# STlinkv21.net
KiCad netlist of a schematic drawn in Altium Designer
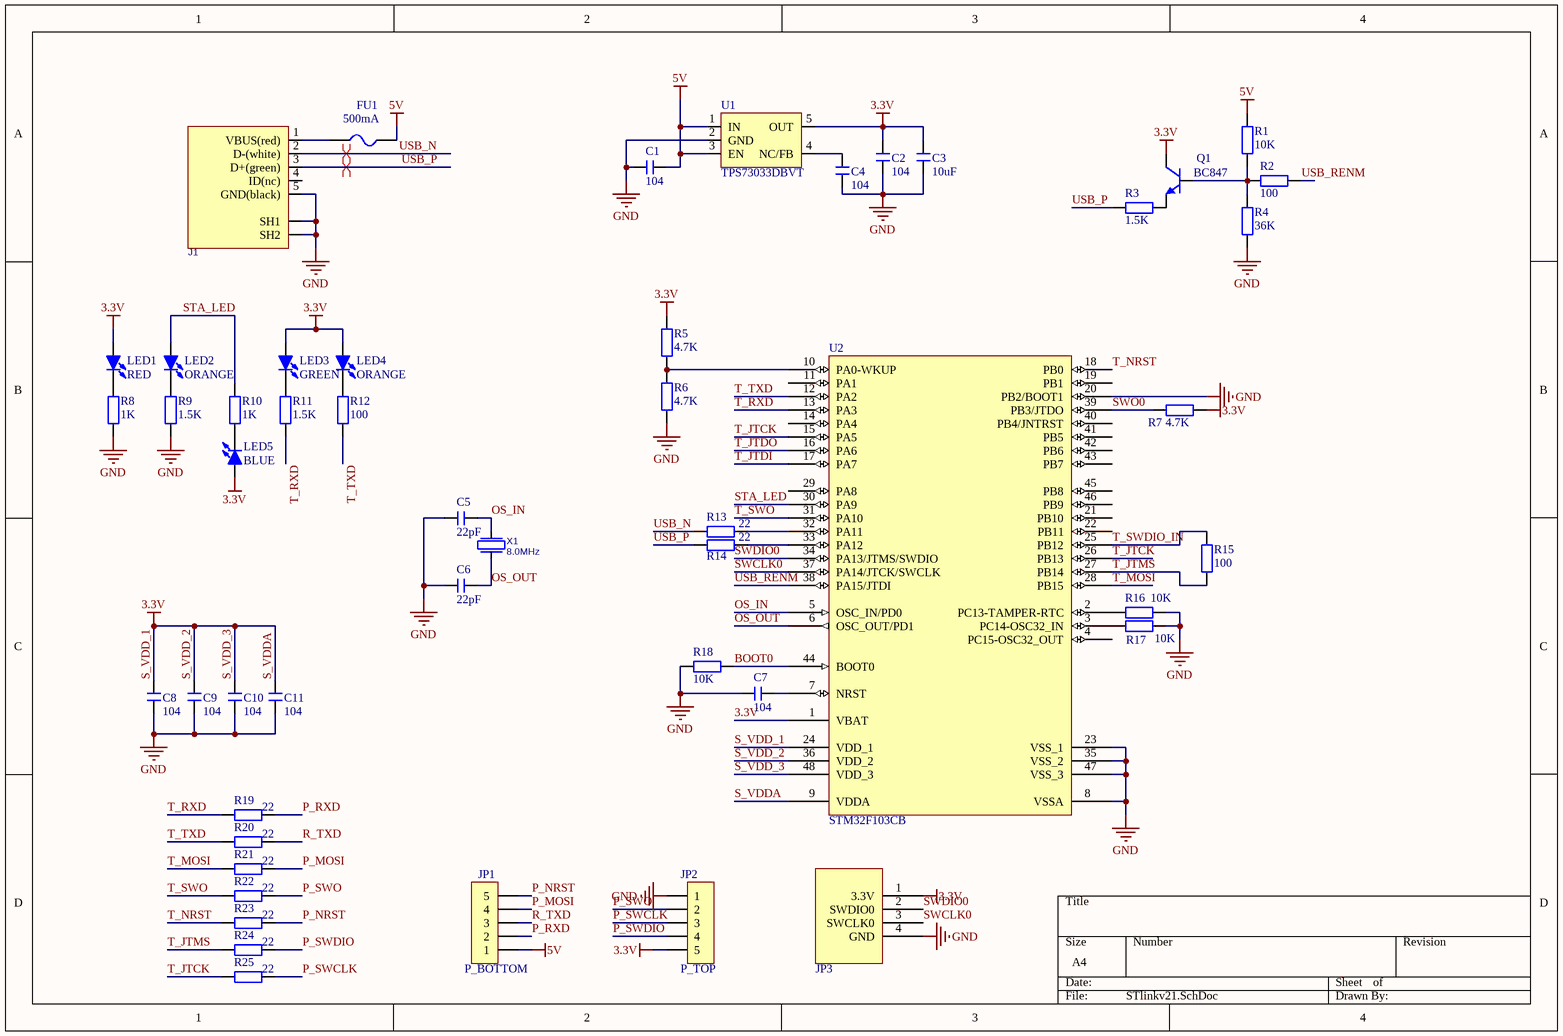
[diagram p0: STlinkv21.SchDoc]

(export (version "E")
  (design (tool "Eeschema 10.0.6"))
  (components
    (comp (ref "*") (value "JP3") (footprint "JP4") (libsource (lib "STlinkv21") (part "JP?")))
    (comp (ref "C1")
      (value "104")
      (footprint "C 0603_L")
      (description "无极性贴片电容")
      (fields (field (name "版权归属") "源创客"))
      (libsource (lib "3.1   - 电阻-电容-电感") (part "C"))
    )
    (comp (ref "C2")
      (value "104")
      (footprint "C 0603_L")
      (description "无极性贴片电容")
      (fields (field (name "版权归属") "源创客"))
      (libsource (lib "3.1   - 电阻-电容-电感") (part "C"))
    )
    (comp (ref "C3")
      (value "10uF")
      (footprint "C 0603_L")
      (description "无极性贴片电容")
      (fields (field (name "版权归属") "源创客"))
      (libsource (lib "3.1   - 电阻-电容-电感") (part "C"))
    )
    (comp (ref "C4")
      (value "104")
      (footprint "C 0603_L")
      (description "无极性贴片电容")
      (fields (field (name "版权归属") "源创客"))
      (libsource (lib "3.1   - 电阻-电容-电感") (part "C"))
    )
    (comp (ref "C5")
      (value "22pF")
      (footprint "C 0603_L")
      (description "无极性贴片电容")
      (fields (field (name "版权归属") "源创客"))
      (libsource (lib "3.1   - 电阻-电容-电感") (part "C"))
    )
    (comp (ref "C6")
      (value "22pF")
      (footprint "C 0603_L")
      (description "无极性贴片电容")
      (fields (field (name "版权归属") "源创客"))
      (libsource (lib "3.1   - 电阻-电容-电感") (part "C"))
    )
    (comp (ref "C7")
      (value "104")
      (footprint "C 0603_L")
      (description "无极性贴片电容")
      (fields (field (name "版权归属") "源创客"))
      (libsource (lib "3.1   - 电阻-电容-电感") (part "C"))
    )
    (comp (ref "C8")
      (value "104")
      (footprint "C 0603_L")
      (description "无极性贴片电容")
      (fields (field (name "版权归属") "源创客"))
      (libsource (lib "3.1   - 电阻-电容-电感") (part "C"))
    )
    (comp (ref "C9")
      (value "104")
      (footprint "C 0603_L")
      (description "无极性贴片电容")
      (fields (field (name "版权归属") "源创客"))
      (libsource (lib "3.1   - 电阻-电容-电感") (part "C"))
    )
    (comp (ref "C10")
      (value "104")
      (footprint "C 0603_L")
      (description "无极性贴片电容")
      (fields (field (name "版权归属") "源创客"))
      (libsource (lib "3.1   - 电阻-电容-电感") (part "C"))
    )
    (comp (ref "C11")
      (value "104")
      (footprint "C 0603_L")
      (description "无极性贴片电容")
      (fields (field (name "版权归属") "源创客"))
      (libsource (lib "3.1   - 电阻-电容-电感") (part "C"))
    )
    (comp (ref "FU1")
      (value "500mA")
      (footprint "FU 0805")
      (description "贴片保险丝")
      (fields (field (name "版权归属") "源创客"))
      (libsource (lib "10.1 - 保险丝-晶振") (part "FU"))
    )
    (comp (ref "J1")
      (value "microUSB 5BFR")
      (footprint "usbmicro B")
      (fields (field (name "LIBRARYNAME") "Nikitin (Exeland)"))
      (libsource (lib "Nikitin") (part "microUSB 5BFR"))
    )
    (comp (ref "JP1")
      (value "P_BOTTOM")
      (footprint "JP5Bottom")
      (description "5P接插件")
      (fields (field (name "版权归属") "源创客"))
      (libsource (lib "") (part "Header 5_1"))
    )
    (comp (ref "JP2")
      (value "P_TOP")
      (footprint "JP5TOP")
      (description "5P接插件")
      (fields (field (name "版权归属") "源创客"))
      (libsource (lib "4.5   - 接插件-脚距2.54") (part "Header 5"))
    )
    (comp (ref "LED1")
      (value "RED")
      (footprint "LED 0603B")
      (description "贴片LED")
      (fields (field (name "版权归属") "源创客"))
      (libsource (lib "9.1   - LED") (part "LED-SMD"))
    )
    (comp (ref "LED2")
      (value "ORANGE")
      (footprint "LED 0603B")
      (description "贴片LED")
      (fields (field (name "版权归属") "源创客"))
      (libsource (lib "9.1   - LED") (part "LED-SMD"))
    )
    (comp (ref "LED3")
      (value "GREEN")
      (footprint "LED 0603B")
      (description "贴片LED")
      (fields (field (name "版权归属") "源创客"))
      (libsource (lib "9.1   - LED") (part "LED-SMD"))
    )
    (comp (ref "LED4")
      (value "ORANGE")
      (footprint "LED 0603B")
      (description "贴片LED")
      (fields (field (name "版权归属") "源创客"))
      (libsource (lib "9.1   - LED") (part "LED-SMD"))
    )
    (comp (ref "LED5")
      (value "BLUE")
      (footprint "LED 0603B")
      (description "贴片LED")
      (fields (field (name "版权归属") "LED 0603 BLUE"))
      (libsource (lib "9.1   - LED") (part "LED-SMD"))
    )
    (comp (ref "Q1")
      (value "BC847")
      (footprint "SOT23-3N")
      (description "高频放大-NPN型")
      (fields (field (name "版权归属") "源创客"))
      (libsource (lib "6.2   - 三极管") (part "8050-SMD"))
    )
    (comp (ref "R1")
      (value "10K")
      (footprint "R 0603_L")
      (description "贴片电阻")
      (fields (field (name "版权归属") "源创客"))
      (libsource (lib "3.1   - 电阻-电容-电感") (part "R"))
    )
    (comp (ref "R2")
      (value "100")
      (footprint "R 0603_L")
      (description "贴片电阻")
      (fields (field (name "版权归属") "源创客"))
      (libsource (lib "3.1   - 电阻-电容-电感") (part "R"))
    )
    (comp (ref "R3")
      (value "1.5K")
      (footprint "R 0603_L")
      (description "贴片电阻")
      (fields (field (name "版权归属") "源创客"))
      (libsource (lib "3.1   - 电阻-电容-电感") (part "R"))
    )
    (comp (ref "R4")
      (value "36K")
      (footprint "R 0603_L")
      (description "贴片电阻")
      (fields (field (name "版权归属") "源创客"))
      (libsource (lib "3.1   - 电阻-电容-电感") (part "R"))
    )
    (comp (ref "R5")
      (value "4.7K")
      (footprint "R 0603_L")
      (description "贴片电阻")
      (fields (field (name "版权归属") "源创客"))
      (libsource (lib "3.1   - 电阻-电容-电感") (part "R"))
    )
    (comp (ref "R6")
      (value "4.7K")
      (footprint "R 0603_L")
      (description "贴片电阻")
      (fields (field (name "版权归属") "源创客"))
      (libsource (lib "3.1   - 电阻-电容-电感") (part "R"))
    )
    (comp (ref "R7")
      (value "4.7K")
      (footprint "R 0603_L")
      (description "贴片电阻")
      (fields (field (name "版权归属") "源创客"))
      (libsource (lib "3.1   - 电阻-电容-电感") (part "R"))
    )
    (comp (ref "R8")
      (value "1K")
      (footprint "R 0603_L")
      (description "贴片电阻")
      (fields (field (name "版权归属") "源创客"))
      (libsource (lib "3.1   - 电阻-电容-电感") (part "R"))
    )
    (comp (ref "R9")
      (value "1.5K")
      (footprint "R 0603_L")
      (description "贴片电阻")
      (fields (field (name "版权归属") "源创客"))
      (libsource (lib "3.1   - 电阻-电容-电感") (part "R"))
    )
    (comp (ref "R10")
      (value "1K")
      (footprint "R 0603_L")
      (description "贴片电阻")
      (fields (field (name "版权归属") "源创客"))
      (libsource (lib "3.1   - 电阻-电容-电感") (part "R"))
    )
    (comp (ref "R11")
      (value "1.5K")
      (footprint "R 0603_L")
      (description "贴片电阻")
      (fields (field (name "版权归属") "源创客"))
      (libsource (lib "3.1   - 电阻-电容-电感") (part "R"))
    )
    (comp (ref "R12")
      (value "100")
      (footprint "R 0603_L")
      (description "贴片电阻")
      (fields (field (name "版权归属") "源创客"))
      (libsource (lib "3.1   - 电阻-电容-电感") (part "R"))
    )
    (comp (ref "R13")
      (value "22")
      (footprint "R 0603_L")
      (description "贴片电阻")
      (fields (field (name "版权归属") "源创客"))
      (libsource (lib "3.1   - 电阻-电容-电感") (part "R"))
    )
    (comp (ref "R14")
      (value "22")
      (footprint "R 0603_L")
      (description "贴片电阻")
      (fields (field (name "版权归属") "源创客"))
      (libsource (lib "3.1   - 电阻-电容-电感") (part "R"))
    )
    (comp (ref "R15")
      (value "100")
      (footprint "R 0603_L")
      (description "贴片电阻")
      (fields (field (name "版权归属") "源创客"))
      (libsource (lib "3.1   - 电阻-电容-电感") (part "R"))
    )
    (comp (ref "R16")
      (value "10K")
      (footprint "R 0603_L")
      (description "贴片电阻")
      (fields (field (name "版权归属") "源创客"))
      (libsource (lib "3.1   - 电阻-电容-电感") (part "R"))
    )
    (comp (ref "R17")
      (value "10K")
      (footprint "R 0603_L")
      (description "贴片电阻")
      (fields (field (name "版权归属") "源创客"))
      (libsource (lib "3.1   - 电阻-电容-电感") (part "R"))
    )
    (comp (ref "R18")
      (value "10K")
      (footprint "R 0603_L")
      (description "贴片电阻")
      (fields (field (name "版权归属") "源创客"))
      (libsource (lib "3.1   - 电阻-电容-电感") (part "R"))
    )
    (comp (ref "R19")
      (value "22")
      (footprint "R 0603_L")
      (description "贴片电阻")
      (fields (field (name "版权归属") "源创客"))
      (libsource (lib "3.1   - 电阻-电容-电感") (part "R"))
    )
    (comp (ref "R20")
      (value "22")
      (footprint "R 0603_L")
      (description "贴片电阻")
      (fields (field (name "版权归属") "源创客"))
      (libsource (lib "3.1   - 电阻-电容-电感") (part "R"))
    )
    (comp (ref "R21")
      (value "22")
      (footprint "R 0603_L")
      (description "贴片电阻")
      (fields (field (name "版权归属") "源创客"))
      (libsource (lib "3.1   - 电阻-电容-电感") (part "R"))
    )
    (comp (ref "R22")
      (value "22")
      (footprint "R 0603_L")
      (description "贴片电阻")
      (fields (field (name "版权归属") "源创客"))
      (libsource (lib "3.1   - 电阻-电容-电感") (part "R"))
    )
    (comp (ref "R23")
      (value "22")
      (footprint "R 0603_L")
      (description "贴片电阻")
      (fields (field (name "版权归属") "源创客"))
      (libsource (lib "3.1   - 电阻-电容-电感") (part "R"))
    )
    (comp (ref "R24")
      (value "22")
      (footprint "R 0603_L")
      (description "贴片电阻")
      (fields (field (name "版权归属") "源创客"))
      (libsource (lib "3.1   - 电阻-电容-电感") (part "R"))
    )
    (comp (ref "R25")
      (value "22")
      (footprint "R 0603_L")
      (description "贴片电阻")
      (fields (field (name "版权归属") "源创客"))
      (libsource (lib "3.1   - 电阻-电容-电感") (part "R"))
    )
    (comp (ref "U1")
      (value "TPS73033DBVT")
      (footprint "SOT-23-5")
      (fields (field (name "LIBRARYNAME") "Nikitin (Exeland)"))
      (libsource (lib "Nikitin") (part "TPS73033DBVT"))
    )
    (comp (ref "U2")
      (value "STM32F103CB")
      (footprint "LQFP48 7X7_L")
      (description "Flaah:64/RAM:20/IO:36")
      (fields (field (name "版权归属") "源创客"))
      (libsource (lib "2.1   - STM32系列单片机") (part "STM32F103C8"))
    )
    (comp (ref "X1")
      (value "8.0MHz")
      (footprint "HC49SMD")
      (description "8 MHz ±20ppm Crystal 18pF 80 Ohms HC-49/US")
      (fields (field (name "Comment") "HC49SM") (field (name "LIBRARYNAME") "Nikitin (Exeland)"))
      (libsource (lib "Nikitin") (part "HC49SM"))
    )
  )
  (nets
    (net (code "1") (name "/BOOT0") (class "Default")
      (node (ref "R18") (pin "1") (pinfunction "1_1") (pintype "passive"))
      (node (ref "U2") (pin "44") (pinfunction "BOOT0_44") (pintype "input"))
    )
    (net (code "2") (name "/OS_IN") (class "Default")
      (node (ref "C5") (pin "2") (pinfunction "2_2") (pintype "passive"))
      (node (ref "U2") (pin "5") (pinfunction "OSC_IN/PD0_5") (pintype "input"))
      (node (ref "X1") (pin "2") (pintype "passive"))
    )
    (net (code "3") (name "/OS_OUT") (class "Default")
      (node (ref "C6") (pin "2") (pinfunction "2_2") (pintype "passive"))
      (node (ref "U2") (pin "6") (pinfunction "OSC_OUT/PD1_6") (pintype "output"))
      (node (ref "X1") (pin "1") (pintype "passive"))
    )
    (net (code "4") (name "/P_MOSI") (class "Default")
      (node (ref "JP1") (pin "4") (pinfunction "4_4") (pintype "passive"))
      (node (ref "R21") (pin "1") (pinfunction "1_1") (pintype "passive"))
    )
    (net (code "5") (name "/P_NRST") (class "Default")
      (node (ref "JP1") (pin "5") (pinfunction "5_5") (pintype "passive"))
      (node (ref "R23") (pin "1") (pinfunction "1_1") (pintype "passive"))
    )
    (net (code "6") (name "/P_RXD") (class "Default")
      (node (ref "JP1") (pin "2") (pinfunction "2_2") (pintype "passive"))
      (node (ref "R19") (pin "1") (pinfunction "1_1") (pintype "passive"))
    )
    (net (code "7") (name "/P_SWCLK") (class "Default")
      (node (ref "JP2") (pin "3") (pinfunction "3_3") (pintype "passive"))
      (node (ref "R25") (pin "1") (pinfunction "1_1") (pintype "passive"))
    )
    (net (code "8") (name "/P_SWDIO") (class "Default")
      (node (ref "JP2") (pin "4") (pinfunction "4_4") (pintype "passive"))
      (node (ref "R24") (pin "1") (pinfunction "1_1") (pintype "passive"))
    )
    (net (code "9") (name "/P_SWO") (class "Default")
      (node (ref "JP2") (pin "2") (pinfunction "2_2") (pintype "passive"))
      (node (ref "R22") (pin "1") (pinfunction "1_1") (pintype "passive"))
    )
    (net (code "10") (name "/R_TXD") (class "Default")
      (node (ref "JP1") (pin "3") (pinfunction "3_3") (pintype "passive"))
      (node (ref "R20") (pin "1") (pinfunction "1_1") (pintype "passive"))
    )
    (net (code "11") (name "/STA_LED") (class "Default")
      (node (ref "LED2") (pin "1") (pinfunction "A_1") (pintype "passive"))
      (node (ref "R10") (pin "2") (pinfunction "2_2") (pintype "passive"))
      (node (ref "U2") (pin "30") (pinfunction "PA9_30") (pintype "bidirectional"))
    )
    (net (code "12") (name "/SWCLK0") (class "Default")
      (node (ref "*") (pin "3") (pinfunction "SWCLK0_3") (pintype "passive"))
      (node (ref "U2") (pin "37") (pinfunction "PA14/JTCK/SWCLK_37") (pintype "bidirectional"))
    )
    (net (code "13") (name "/SWDIO0") (class "Default")
      (node (ref "*") (pin "2") (pinfunction "SWDIO0_2") (pintype "passive"))
      (node (ref "U2") (pin "34") (pinfunction "PA13/JTMS/SWDIO_34") (pintype "bidirectional"))
    )
    (net (code "14") (name "/SWO0") (class "Default")
      (node (ref "R7") (pin "1") (pinfunction "1_1") (pintype "passive"))
      (node (ref "U2") (pin "39") (pinfunction "PB3/JTDO_39") (pintype "bidirectional"))
    )
    (net (code "15") (name "/T_JTCK") (class "Default")
      (node (ref "R25") (pin "2") (pinfunction "2_2") (pintype "passive"))
      (node (ref "U2") (pin "15") (pinfunction "PA5_15") (pintype "bidirectional"))
      (node (ref "U2") (pin "26") (pinfunction "PB13_26") (pintype "bidirectional"))
    )
    (net (code "16") (name "/T_JTDI") (class "Default")
      (node (ref "U2") (pin "17") (pinfunction "PA7_17") (pintype "bidirectional"))
    )
    (net (code "17") (name "/T_JTDO") (class "Default")
      (node (ref "U2") (pin "16") (pinfunction "PA6_16") (pintype "bidirectional"))
    )
    (net (code "18") (name "/T_JTMS") (class "Default")
      (node (ref "R15") (pin "2") (pinfunction "2_2") (pintype "passive"))
      (node (ref "R24") (pin "2") (pinfunction "2_2") (pintype "passive"))
      (node (ref "U2") (pin "27") (pinfunction "PB14_27") (pintype "bidirectional"))
    )
    (net (code "19") (name "/T_MOSI") (class "Default")
      (node (ref "R21") (pin "2") (pinfunction "2_2") (pintype "passive"))
      (node (ref "U2") (pin "28") (pinfunction "PB15_28") (pintype "bidirectional"))
    )
    (net (code "20") (name "/T_NRST") (class "Default")
      (node (ref "R23") (pin "2") (pinfunction "2_2") (pintype "passive"))
      (node (ref "U2") (pin "18") (pinfunction "PB0_18") (pintype "bidirectional"))
    )
    (net (code "21") (name "/T_RXD") (class "Default")
      (node (ref "R11") (pin "1") (pinfunction "1_1") (pintype "passive"))
      (node (ref "R19") (pin "2") (pinfunction "2_2") (pintype "passive"))
      (node (ref "U2") (pin "13") (pinfunction "PA3_13") (pintype "bidirectional"))
    )
    (net (code "22") (name "/T_SWDIO_IN") (class "Default")
      (node (ref "R15") (pin "1") (pinfunction "1_1") (pintype "passive"))
      (node (ref "U2") (pin "25") (pinfunction "PB12_25") (pintype "bidirectional"))
    )
    (net (code "23") (name "/T_SWO") (class "Default")
      (node (ref "R22") (pin "2") (pinfunction "2_2") (pintype "passive"))
      (node (ref "U2") (pin "31") (pinfunction "PA10_31") (pintype "bidirectional"))
    )
    (net (code "24") (name "/T_TXD") (class "Default")
      (node (ref "R12") (pin "1") (pinfunction "1_1") (pintype "passive"))
      (node (ref "R20") (pin "2") (pinfunction "2_2") (pintype "passive"))
      (node (ref "U2") (pin "12") (pinfunction "PA2_12") (pintype "bidirectional"))
    )
    (net (code "25") (name "/USB_N") (class "Default")
      (node (ref "J1") (pin "2") (pinfunction "D-(white)_2") (pintype "passive"))
      (node (ref "R13") (pin "2") (pinfunction "2_2") (pintype "passive"))
    )
    (net (code "26") (name "/USB_P") (class "Default")
      (node (ref "J1") (pin "3") (pinfunction "D+(green)_3") (pintype "passive"))
      (node (ref "R14") (pin "2") (pinfunction "2_2") (pintype "passive"))
      (node (ref "R3") (pin "1") (pinfunction "1_1") (pintype "passive"))
    )
    (net (code "27") (name "/USB_RENM") (class "Default")
      (node (ref "R2") (pin "2") (pinfunction "2_2") (pintype "passive"))
      (node (ref "U2") (pin "38") (pinfunction "PA15/JTDI_38") (pintype "bidirectional"))
    )
    (net (code "28") (name "3.3V") (class "Default")
      (node (ref "*") (pin "1") (pinfunction "3.3V_1") (pintype "passive"))
      (node (ref "C10") (pin "2") (pinfunction "2_2") (pintype "passive"))
      (node (ref "C11") (pin "2") (pinfunction "2_2") (pintype "passive"))
      (node (ref "C2") (pin "2") (pinfunction "2_2") (pintype "passive"))
      (node (ref "C3") (pin "2") (pinfunction "2_2") (pintype "passive"))
      (node (ref "C8") (pin "2") (pinfunction "2_2") (pintype "passive"))
      (node (ref "C9") (pin "2") (pinfunction "2_2") (pintype "passive"))
      (node (ref "JP2") (pin "5") (pinfunction "5_5") (pintype "passive"))
      (node (ref "LED1") (pin "1") (pinfunction "A_1") (pintype "passive"))
      (node (ref "LED3") (pin "1") (pinfunction "A_1") (pintype "passive"))
      (node (ref "LED4") (pin "1") (pinfunction "A_1") (pintype "passive"))
      (node (ref "LED5") (pin "1") (pinfunction "A_1") (pintype "passive"))
      (node (ref "Q1") (pin "3") (pinfunction "C_3") (pintype "passive"))
      (node (ref "R5") (pin "2") (pinfunction "2_2") (pintype "passive"))
      (node (ref "R7") (pin "2") (pinfunction "2_2") (pintype "passive"))
      (node (ref "U1") (pin "5") (pinfunction "OUT_5") (pintype "passive"))
      (node (ref "U2") (pin "1") (pinfunction "VBAT_1") (pintype "power_in"))
      (node (ref "U2") (pin "24") (pinfunction "VDD_1_24") (pintype "power_in"))
      (node (ref "U2") (pin "36") (pinfunction "VDD_2_36") (pintype "power_in"))
      (node (ref "U2") (pin "48") (pinfunction "VDD_3_48") (pintype "power_in"))
      (node (ref "U2") (pin "9") (pinfunction "VDDA_9") (pintype "power_in"))
    )
    (net (code "29") (name "5V") (class "Default")
      (node (ref "C1") (pin "2") (pinfunction "2_2") (pintype "passive"))
      (node (ref "FU1") (pin "2") (pinfunction "2_2") (pintype "passive"))
      (node (ref "JP1") (pin "1") (pinfunction "1_1") (pintype "passive"))
      (node (ref "R1") (pin "2") (pinfunction "2_2") (pintype "passive"))
      (node (ref "U1") (pin "1") (pinfunction "IN_1") (pintype "passive"))
      (node (ref "U1") (pin "3") (pinfunction "EN_3") (pintype "passive"))
    )
    (net (code "30") (name "GND") (class "Default")
      (node (ref "*") (pin "4") (pinfunction "GND_4") (pintype "passive"))
      (node (ref "C1") (pin "1") (pinfunction "1_1") (pintype "passive"))
      (node (ref "C10") (pin "1") (pinfunction "1_1") (pintype "passive"))
      (node (ref "C11") (pin "1") (pinfunction "1_1") (pintype "passive"))
      (node (ref "C2") (pin "1") (pinfunction "1_1") (pintype "passive"))
      (node (ref "C3") (pin "1") (pinfunction "1_1") (pintype "passive"))
      (node (ref "C4") (pin "1") (pinfunction "1_1") (pintype "passive"))
      (node (ref "C5") (pin "1") (pinfunction "1_1") (pintype "passive"))
      (node (ref "C6") (pin "1") (pinfunction "1_1") (pintype "passive"))
      (node (ref "C7") (pin "1") (pinfunction "1_1") (pintype "passive"))
      (node (ref "C8") (pin "1") (pinfunction "1_1") (pintype "passive"))
      (node (ref "C9") (pin "1") (pinfunction "1_1") (pintype "passive"))
      (node (ref "J1") (pin "11") (pinfunction "SH2_11") (pintype "passive"))
      (node (ref "J1") (pin "5") (pinfunction "GND(black)_5") (pintype "passive"))
      (node (ref "J1") (pin "8") (pinfunction "SH1_8") (pintype "passive"))
      (node (ref "JP2") (pin "1") (pinfunction "1_1") (pintype "passive"))
      (node (ref "R16") (pin "1") (pinfunction "1_1") (pintype "passive"))
      (node (ref "R17") (pin "1") (pinfunction "1_1") (pintype "passive"))
      (node (ref "R18") (pin "2") (pinfunction "2_2") (pintype "passive"))
      (node (ref "R4") (pin "1") (pinfunction "1_1") (pintype "passive"))
      (node (ref "R6") (pin "1") (pinfunction "1_1") (pintype "passive"))
      (node (ref "R8") (pin "1") (pinfunction "1_1") (pintype "passive"))
      (node (ref "R9") (pin "1") (pinfunction "1_1") (pintype "passive"))
      (node (ref "U1") (pin "2") (pinfunction "GND_2") (pintype "passive"))
      (node (ref "U2") (pin "20") (pinfunction "PB2/BOOT1_20") (pintype "bidirectional"))
      (node (ref "U2") (pin "23") (pinfunction "VSS_1_23") (pintype "power_in"))
      (node (ref "U2") (pin "35") (pinfunction "VSS_2_35") (pintype "power_in"))
      (node (ref "U2") (pin "47") (pinfunction "VSS_3_47") (pintype "power_in"))
      (node (ref "U2") (pin "8") (pinfunction "VSSA_8") (pintype "power_in"))
    )
    (net (code "31") (name "Net-(J1-VBUS(red))") (class "Default")
      (node (ref "FU1") (pin "1") (pinfunction "1_1") (pintype "passive"))
      (node (ref "J1") (pin "1") (pinfunction "VBUS(red)_1") (pintype "passive"))
    )
    (net (code "32") (name "Net-(LED1-K)") (class "Default")
      (node (ref "LED1") (pin "2") (pinfunction "K_2") (pintype "passive"))
      (node (ref "R8") (pin "2") (pinfunction "2_2") (pintype "passive"))
    )
    (net (code "33") (name "Net-(LED2-K)") (class "Default")
      (node (ref "LED2") (pin "2") (pinfunction "K_2") (pintype "passive"))
      (node (ref "R9") (pin "2") (pinfunction "2_2") (pintype "passive"))
    )
    (net (code "34") (name "Net-(LED3-K)") (class "Default")
      (node (ref "LED3") (pin "2") (pinfunction "K_2") (pintype "passive"))
      (node (ref "R11") (pin "2") (pinfunction "2_2") (pintype "passive"))
    )
    (net (code "35") (name "Net-(LED4-K)") (class "Default")
      (node (ref "LED4") (pin "2") (pinfunction "K_2") (pintype "passive"))
      (node (ref "R12") (pin "2") (pinfunction "2_2") (pintype "passive"))
    )
    (net (code "36") (name "Net-(LED5-K)") (class "Default")
      (node (ref "LED5") (pin "2") (pinfunction "K_2") (pintype "passive"))
      (node (ref "R10") (pin "1") (pinfunction "1_1") (pintype "passive"))
    )
    (net (code "37") (name "Net-(Q1-B)") (class "Default")
      (node (ref "Q1") (pin "1") (pinfunction "B_1") (pintype "passive"))
      (node (ref "R1") (pin "1") (pinfunction "1_1") (pintype "passive"))
      (node (ref "R2") (pin "1") (pinfunction "1_1") (pintype "passive"))
      (node (ref "R4") (pin "2") (pinfunction "2_2") (pintype "passive"))
    )
    (net (code "38") (name "Net-(Q1-E)") (class "Default")
      (node (ref "Q1") (pin "2") (pinfunction "E_2") (pintype "passive"))
      (node (ref "R3") (pin "2") (pinfunction "2_2") (pintype "passive"))
    )
    (net (code "39") (name "Net-(U1-NC{slash}FB)") (class "Default")
      (node (ref "C4") (pin "2") (pinfunction "2_2") (pintype "passive"))
      (node (ref "U1") (pin "4") (pinfunction "NC/FB_4") (pintype "passive"))
    )
    (net (code "40") (name "Net-(U2-NRST)") (class "Default")
      (node (ref "C7") (pin "2") (pinfunction "2_2") (pintype "passive"))
      (node (ref "U2") (pin "7") (pinfunction "NRST_7") (pintype "bidirectional"))
    )
    (net (code "41") (name "Net-(U2-PA0-WKUP)") (class "Default")
      (node (ref "R5") (pin "1") (pinfunction "1_1") (pintype "passive"))
      (node (ref "R6") (pin "2") (pinfunction "2_2") (pintype "passive"))
      (node (ref "U2") (pin "10") (pinfunction "PA0-WKUP_10") (pintype "bidirectional"))
    )
    (net (code "42") (name "Net-(U2-PA11)") (class "Default")
      (node (ref "R13") (pin "1") (pinfunction "1_1") (pintype "passive"))
      (node (ref "U2") (pin "32") (pinfunction "PA11_32") (pintype "bidirectional"))
    )
    (net (code "43") (name "Net-(U2-PA12)") (class "Default")
      (node (ref "R14") (pin "1") (pinfunction "1_1") (pintype "passive"))
      (node (ref "U2") (pin "33") (pinfunction "PA12_33") (pintype "bidirectional"))
    )
    (net (code "44") (name "Net-(U2-PC13-TAMPER-RTC)") (class "Default")
      (node (ref "R16") (pin "2") (pinfunction "2_2") (pintype "passive"))
      (node (ref "U2") (pin "2") (pinfunction "PC13-TAMPER-RTC_2") (pintype "bidirectional"))
    )
    (net (code "45") (name "Net-(U2-PC14-OSC32_IN)") (class "Default")
      (node (ref "R17") (pin "2") (pinfunction "2_2") (pintype "passive"))
      (node (ref "U2") (pin "3") (pinfunction "PC14-OSC32_IN_3") (pintype "bidirectional"))
    )
    (net (code "46") (name "unconnected-(J1-ID(nc)-Pad4)") (class "Default")
      (node (ref "J1") (pin "4") (pinfunction "ID(nc)_4") (pintype "passive"))
    )
    (net (code "47") (name "unconnected-(U2-PA1-Pad11)") (class "Default")
      (node (ref "U2") (pin "11") (pinfunction "PA1_11") (pintype "bidirectional"))
    )
    (net (code "48") (name "unconnected-(U2-PA4-Pad14)") (class "Default")
      (node (ref "U2") (pin "14") (pinfunction "PA4_14") (pintype "bidirectional"))
    )
    (net (code "49") (name "unconnected-(U2-PA8-Pad29)") (class "Default")
      (node (ref "U2") (pin "29") (pinfunction "PA8_29") (pintype "bidirectional"))
    )
    (net (code "50") (name "unconnected-(U2-PB1-Pad19)") (class "Default")
      (node (ref "U2") (pin "19") (pinfunction "PB1_19") (pintype "bidirectional"))
    )
    (net (code "51") (name "unconnected-(U2-PB4{slash}JNTRST-Pad40)") (class "Default")
      (node (ref "U2") (pin "40") (pinfunction "PB4/JNTRST_40") (pintype "bidirectional"))
    )
    (net (code "52") (name "unconnected-(U2-PB5-Pad41)") (class "Default")
      (node (ref "U2") (pin "41") (pinfunction "PB5_41") (pintype "bidirectional"))
    )
    (net (code "53") (name "unconnected-(U2-PB6-Pad42)") (class "Default")
      (node (ref "U2") (pin "42") (pinfunction "PB6_42") (pintype "bidirectional"))
    )
    (net (code "54") (name "unconnected-(U2-PB7-Pad43)") (class "Default")
      (node (ref "U2") (pin "43") (pinfunction "PB7_43") (pintype "bidirectional"))
    )
    (net (code "55") (name "unconnected-(U2-PB8-Pad45)") (class "Default")
      (node (ref "U2") (pin "45") (pinfunction "PB8_45") (pintype "bidirectional"))
    )
    (net (code "56") (name "unconnected-(U2-PB9-Pad46)") (class "Default")
      (node (ref "U2") (pin "46") (pinfunction "PB9_46") (pintype "bidirectional"))
    )
    (net (code "57") (name "unconnected-(U2-PB10-Pad21)") (class "Default")
      (node (ref "U2") (pin "21") (pinfunction "PB10_21") (pintype "bidirectional"))
    )
    (net (code "58") (name "unconnected-(U2-PB11-Pad22)") (class "Default")
      (node (ref "U2") (pin "22") (pinfunction "PB11_22") (pintype "bidirectional"))
    )
    (net (code "59") (name "unconnected-(U2-PC15-OSC32_OUT-Pad4)") (class "Default")
      (node (ref "U2") (pin "4") (pinfunction "PC15-OSC32_OUT_4") (pintype "bidirectional"))
    )
  )
)
